# PG3_SHEET1.net
KiCad netlist of a schematic drawn in Altium Designer
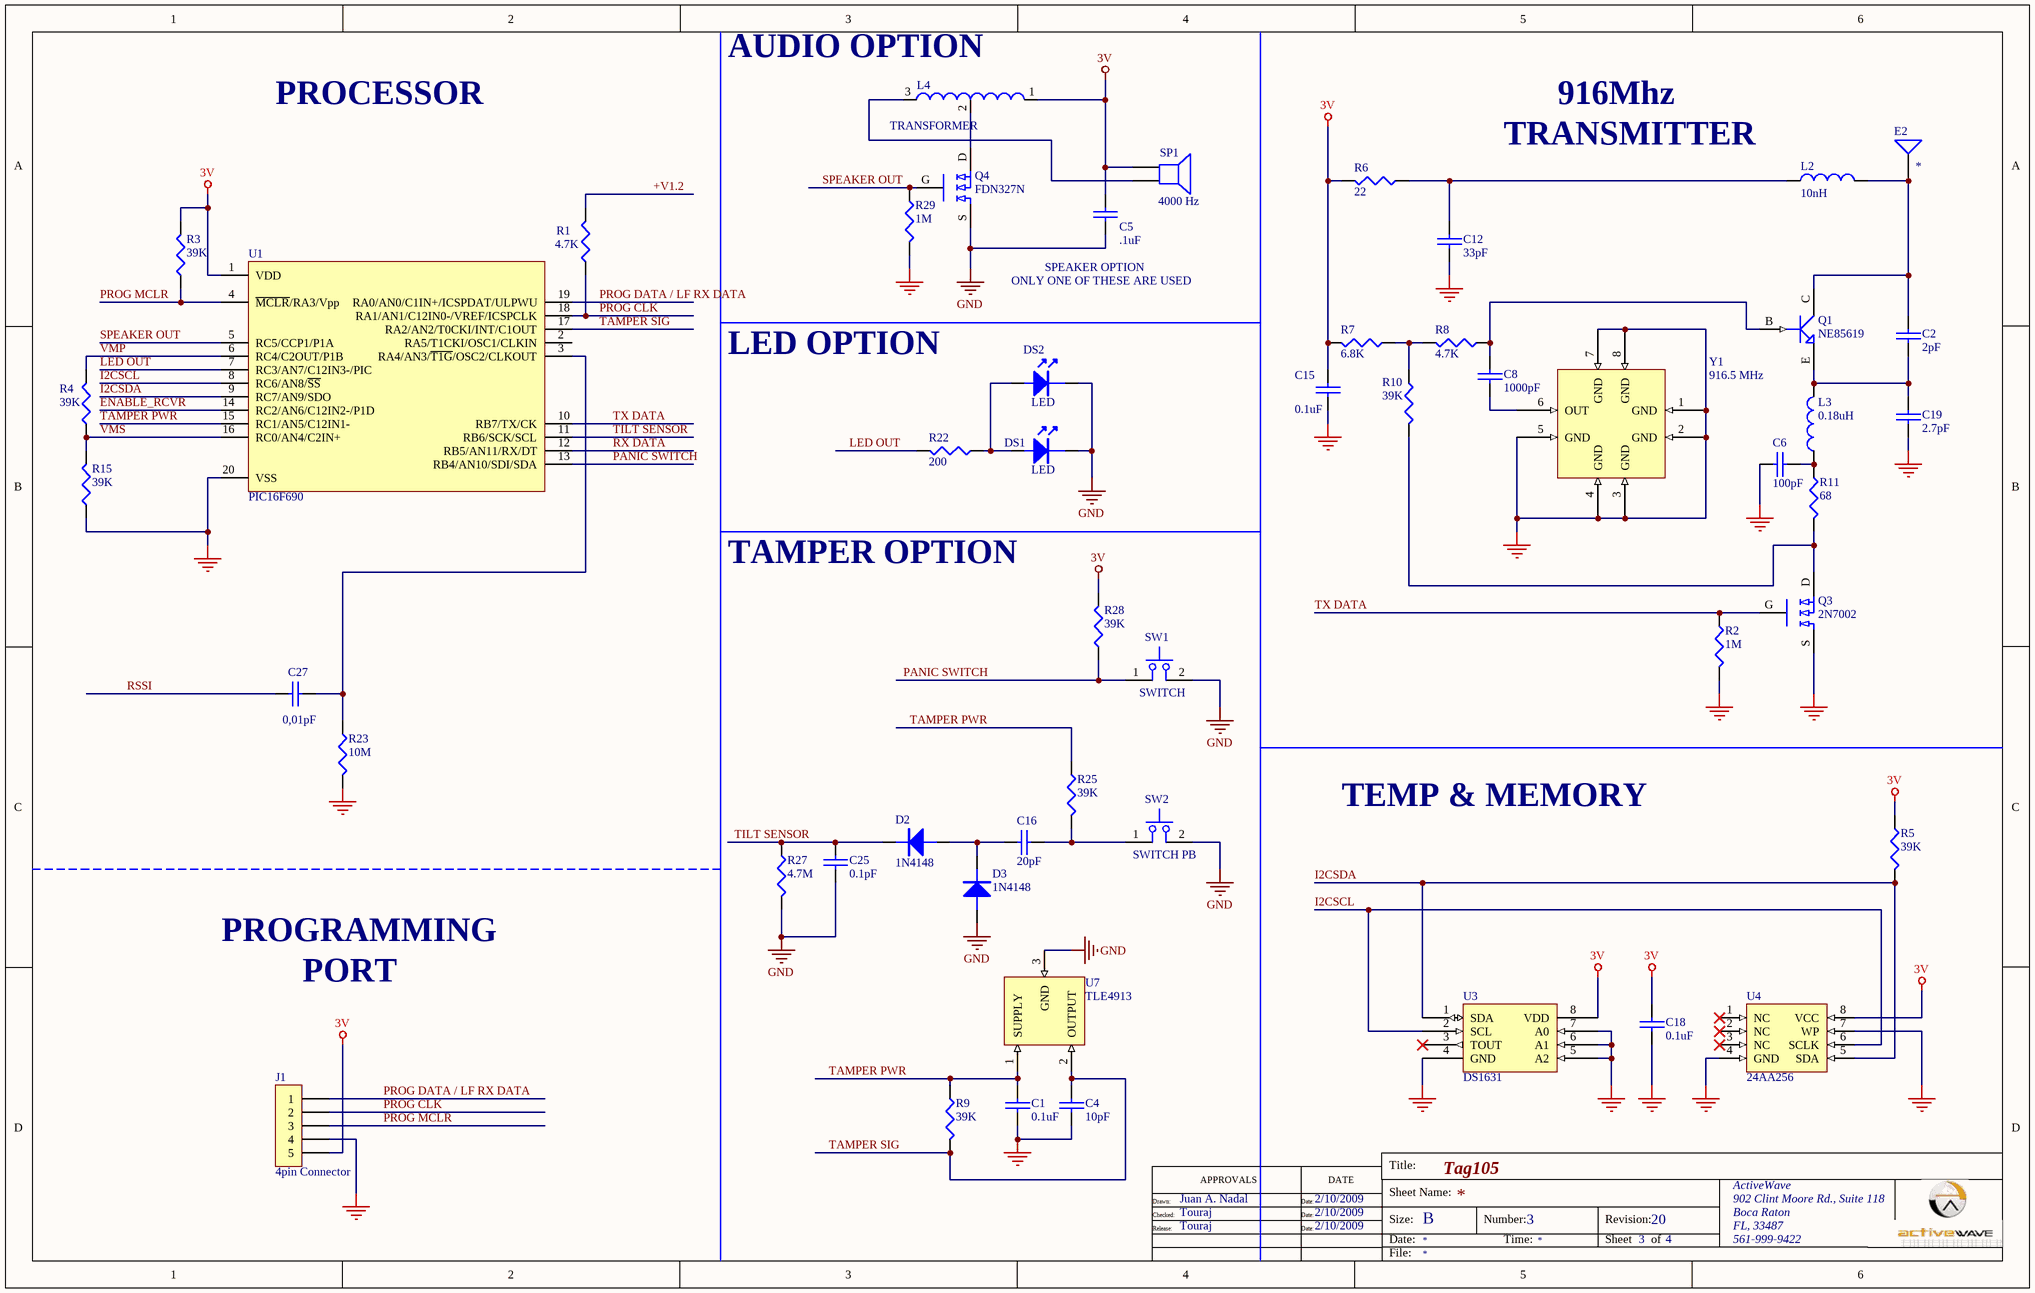
[diagram p0: PG3 SHEET1.schdoc]

(export (version "E")
  (design (tool "Eeschema 10.0.6"))
  (components
    (comp (ref "C1")
      (value "0.1uF")
      (footprint "0603")
      (description "Capacitor")
      (libsource (lib "ActiveWave MasterLib") (part "CAP-0603"))
    )
    (comp (ref "C2")
      (value "2pF")
      (footprint "0603")
      (description "Capacitor")
      (libsource (lib "ActiveWave MasterLib") (part "CAP-0603"))
    )
    (comp (ref "C4")
      (value "10pF")
      (footprint "0603")
      (description "Capacitor")
      (libsource (lib "ActiveWave MasterLib") (part "CAP-0603"))
    )
    (comp (ref "C5")
      (value ".1uF")
      (footprint "0603")
      (description "Capacitor")
      (libsource (lib "ActiveWave MasterLib") (part "CAP-0603"))
    )
    (comp (ref "C6")
      (value "100pF")
      (footprint "0603")
      (description "Capacitor")
      (libsource (lib "ActiveWave MasterLib") (part "CAP-0603"))
    )
    (comp (ref "C8")
      (value "1000pF")
      (footprint "0603")
      (description "Capacitor")
      (libsource (lib "ActiveWave MasterLib") (part "CAP-0603"))
    )
    (comp (ref "C12")
      (value "33pF")
      (footprint "0603")
      (description "Capacitor")
      (libsource (lib "ActiveWave MasterLib") (part "CAP-0603"))
    )
    (comp (ref "C15")
      (value "0.1uF")
      (footprint "0603")
      (description "Capacitor")
      (libsource (lib "ActiveWave MasterLib") (part "CAP-0603"))
    )
    (comp (ref "C16")
      (value "20pF")
      (footprint "0603")
      (description "Capacitor")
      (libsource (lib "ActiveWave MasterLib") (part "CAP-0603"))
    )
    (comp (ref "C18")
      (value "0.1uF")
      (footprint "0603")
      (description "Capacitor")
      (libsource (lib "ActiveWave MasterLib") (part "CAP-0603"))
    )
    (comp (ref "C19")
      (value "2.7pF")
      (footprint "0603")
      (description "Capacitor")
      (libsource (lib "ActiveWave MasterLib") (part "CAP-0603"))
    )
    (comp (ref "C25")
      (value "0.1pF")
      (footprint "0603")
      (description "Capacitor")
      (libsource (lib "ActiveWave MasterLib") (part "CAP-0603"))
    )
    (comp (ref "C27")
      (value "0,01pF")
      (footprint "0603")
      (description "Capacitor")
      (libsource (lib "ActiveWave MasterLib") (part "CAP-0603"))
    )
    (comp (ref "D2")
      (value "1N4148")
      (footprint "sod123_021405")
      (libsource (lib "ActiveWave MasterLib") (part "DIODE"))
    )
    (comp (ref "D3")
      (value "1N4148")
      (footprint "sod123_021405")
      (libsource (lib "ActiveWave MasterLib") (part "DIODE"))
    )
    (comp (ref "DS1")
      (value "LED")
      (footprint "404-1032-2-ND")
      (libsource (lib "ActiveWave MasterLib") (part "LED"))
    )
    (comp (ref "DS2")
      (value "LED")
      (footprint "LCE-358RP")
      (description "X-Bring Red Power SMD LED Emitter")
      (fields (field (name "MANUFACTURER") "L.C. LED"))
      (libsource (lib "ActiveWave MasterLib") (part "LCE-358RP"))
    )
    (comp (ref "E2")
      (value "*")
      (footprint "Antenna1")
      (fields (field (name "ALTIUM_VALUE") "*"))
      (libsource (lib "ActiveWave MasterLib") (part "Antenna1"))
    )
    (comp (ref "J1")
      (value "4pin Connector")
      (footprint "1X5 HEADER")
      (description "Connector")
      (libsource (lib "ActiveWave MasterLib") (part "CON5-1"))
    )
    (comp (ref "L2")
      (value "10nH")
      (footprint "0603")
      (libsource (lib "ActiveWave MasterLib") (part "INDUCTOR"))
    )
    (comp (ref "L3")
      (value "0.18uH")
      (footprint "0603")
      (libsource (lib "ActiveWave MasterLib") (part "INDUCTOR"))
    )
    (comp (ref "L4")
      (value "TRANSFORMER")
      (footprint "COIL_6mmx6mm_011012")
      (libsource (lib "ActiveWave MasterLib") (part "INDUCTOR_V2"))
    )
    (comp (ref "Q1")
      (value "NE85619")
      (footprint "3 PIN ULTRA SUPER MINI MOLD")
      (description "TRANSISTOR NPN 1GHZ SMD")
      (fields (field (name "MANUFACTURER") "??????"))
      (libsource (lib "ActiveWave MasterLib") (part "NE85619"))
    )
    (comp (ref "Q3")
      (value "2N7002")
      (footprint "SOT23 FET")
      (description "N-CHANNEL ENHANCEMENT MODE FIELD EFFECT TRANSISTOR")
      (fields (field (name "MANUFACTURER") "FAIRCHILD"))
      (libsource (lib "ActiveWave MasterLib") (part "2N7002"))
    )
    (comp (ref "Q4")
      (value "FDN327N")
      (footprint "SOT23 FET")
      (description "20V N-Channel MOSFET")
      (fields (field (name "MANUFACTURER") "FAIRCHILD"))
      (libsource (lib "ActiveWave MasterLib") (part "FDN327N"))
    )
    (comp (ref "R1") (value "4.7K") (footprint "0603") (libsource (lib "*") (part "RESISTOR")))
    (comp (ref "R2") (value "1M") (libsource (lib "ActiveWave MasterLib") (part "RES-0402")))
    (comp (ref "R3")
      (value "39K")
      (footprint "0603")
      (libsource (lib "ActiveWave MasterLib") (part "RES-0603"))
    )
    (comp (ref "R4")
      (value "39K")
      (footprint "0603")
      (libsource (lib "ActiveWave MasterLib") (part "RES-0603"))
    )
    (comp (ref "R5")
      (value "39K")
      (footprint "0603")
      (libsource (lib "ActiveWave MasterLib") (part "RES-0603"))
    )
    (comp (ref "R6") (value "22") (libsource (lib "ActiveWave MasterLib") (part "RES-0402")))
    (comp (ref "R7") (value "6.8K") (libsource (lib "ActiveWave MasterLib") (part "RES-0402")))
    (comp (ref "R8") (value "4.7K") (libsource (lib "ActiveWave MasterLib") (part "RES-0402")))
    (comp (ref "R9")
      (value "39K")
      (footprint "0603")
      (libsource (lib "ActiveWave MasterLib") (part "RES-0603"))
    )
    (comp (ref "R10")
      (value "39K")
      (footprint "0603")
      (libsource (lib "ActiveWave MasterLib") (part "RES-0603"))
    )
    (comp (ref "R11") (value "68") (libsource (lib "ActiveWave MasterLib") (part "RES-0402")))
    (comp (ref "R15")
      (value "39K")
      (footprint "0603")
      (libsource (lib "ActiveWave MasterLib") (part "RES-0603"))
    )
    (comp (ref "R22")
      (value "200")
      (footprint "0603")
      (libsource (lib "ActiveWave MasterLib") (part "RES-0603"))
    )
    (comp (ref "R23")
      (value "10M")
      (footprint "0603")
      (libsource (lib "ActiveWave MasterLib") (part "RES-0603"))
    )
    (comp (ref "R25")
      (value "39K")
      (footprint "0603")
      (libsource (lib "ActiveWave MasterLib") (part "RES-0603"))
    )
    (comp (ref "R27")
      (value "4.7M")
      (footprint "0603")
      (libsource (lib "ActiveWave MasterLib") (part "RES-0603"))
    )
    (comp (ref "R28")
      (value "39K")
      (footprint "0603")
      (libsource (lib "ActiveWave MasterLib") (part "RES-0603"))
    )
    (comp (ref "R29")
      (value "1M")
      (footprint "0603")
      (libsource (lib "ActiveWave MasterLib") (part "RES-0402"))
    )
    (comp (ref "SP1")
      (value "4000 Hz")
      (footprint "SPEAKER 12mmx12mm_011012")
      (description "Surface Mount Transducer")
      (fields (field (name "MANUFACTURER") "PUI Audio"))
      (libsource (lib "ActiveWave MasterLib") (part "SMT-1028-S-R"))
    )
    (comp (ref "SW1")
      (value "SWITCH")
      (footprint "SWITCH PB REVERSED_082907")
      (libsource (lib "ActiveWave MasterLib") (part "SWITCH"))
    )
    (comp (ref "SW2")
      (value "SWITCH PB")
      (footprint "SQ-SEN-200")
      (libsource (lib "ActiveWave MasterLib") (part "SWITCH PB"))
    )
    (comp (ref "U1")
      (value "PIC16F690")
      (footprint "SSOP20 WIDE")
      (description "Microcontrollers (MCU) 7KB FL 256R 18 I/O")
      (fields (field (name "MANUFACTURER") "Microchip"))
      (libsource (lib "ActiveWave MasterLib") (part "PIC16F690-E/P"))
    )
    (comp (ref "U3")
      (value "DS1631")
      (footprint "SO8 SMALL")
      (description "High-Precision Digital Thermometer and Thermostat")
      (fields (field (name "MANUFACTURER") "DALLAS SEMICONDUCTOR"))
      (libsource (lib "ActiveWave MasterLib") (part "DS1631"))
    )
    (comp (ref "U4")
      (value "24AA256")
      (footprint "SO8")
      (description "24AA256 32k Microchip Serial EEPROM")
      (fields (field (name "MANUFACTURER") "Microchip"))
      (libsource (lib "ActiveWave MasterLib") (part "24AA256-I/P"))
    )
    (comp (ref "U7")
      (value "TLE4913")
      (footprint "SOT23W")
      (description "Low Power Hall Switch")
      (fields (field (name "MANUFACTURER") "Infineon Technologies AG"))
      (libsource (lib "ActiveWave MasterLib") (part "TLE4913"))
    )
    (comp (ref "Y1")
      (value "916.5 MHz")
      (footprint "RESONATOR")
      (description "916.5 MHz Saw Resonator")
      (fields (field (name "MANUFACTURER") "??????"))
      (libsource (lib "ActiveWave MasterLib") (part "RESONATOR"))
    )
  )
  (nets
    (net (code "1") (name "/+V1.2") (class "Default")
      (node (ref "R1") (pin "2") (pinfunction "2_2") (pintype "passive"))
    )
    (net (code "2") (name "/ENABLE_RCVR") (class "Default")
      (node (ref "U1") (pin "14") (pinfunction "RC2/AN6/C12IN2-/P1D_14") (pintype "passive"))
    )
    (net (code "3") (name "/I2CSCL") (class "Default")
      (node (ref "U1") (pin "8") (pinfunction "RC6/AN8/~{SS}_8") (pintype "passive"))
      (node (ref "U3") (pin "2") (pinfunction "SCL_2") (pintype "input"))
      (node (ref "U4") (pin "6") (pinfunction "SCLK_6") (pintype "input"))
    )
    (net (code "4") (name "/I2CSDA") (class "Default")
      (node (ref "R5") (pin "2") (pinfunction "2_2") (pintype "passive"))
      (node (ref "U1") (pin "9") (pinfunction "RC7/AN9/SDO_9") (pintype "passive"))
      (node (ref "U3") (pin "1") (pinfunction "SDA_1") (pintype "bidirectional"))
      (node (ref "U4") (pin "5") (pinfunction "SDA_5") (pintype "input"))
    )
    (net (code "5") (name "/LED OUT") (class "Default")
      (node (ref "R22") (pin "2") (pinfunction "2_2") (pintype "passive"))
      (node (ref "U1") (pin "7") (pinfunction "RC3/AN7/C12IN3-/PIC_7") (pintype "passive"))
    )
    (net (code "6") (name "/PANIC SWITCH") (class "Default")
      (node (ref "R28") (pin "1") (pinfunction "1_1") (pintype "passive"))
      (node (ref "SW1") (pin "1") (pinfunction "1_1") (pintype "passive"))
      (node (ref "U1") (pin "13") (pinfunction "RB4/AN10/SDI/SDA_13") (pintype "passive"))
    )
    (net (code "7") (name "/PROG CLK") (class "Default")
      (node (ref "J1") (pin "2") (pinfunction "2_2") (pintype "passive"))
      (node (ref "R1") (pin "1") (pinfunction "1_1") (pintype "passive"))
      (node (ref "U1") (pin "18") (pinfunction "RA1/AN1/C12IN0-/VREF/ICSPCLK_18") (pintype "passive"))
    )
    (net (code "8") (name "/PROG DATA {slash} LF RX DATA") (class "Default")
      (node (ref "J1") (pin "1") (pinfunction "1_1") (pintype "passive"))
      (node (ref "U1") (pin "19") (pinfunction "RA0/AN0/C1IN+/ICSPDAT/ULPWU_19") (pintype "passive"))
    )
    (net (code "9") (name "/PROG MCLR") (class "Default")
      (node (ref "J1") (pin "3") (pinfunction "3_3") (pintype "passive"))
      (node (ref "R3") (pin "1") (pinfunction "1_1") (pintype "passive"))
      (node (ref "U1") (pin "4") (pinfunction "~{MCLR}/RA3/Vpp_4") (pintype "passive"))
    )
    (net (code "10") (name "/RSSI") (class "Default")
      (node (ref "C27") (pin "1") (pinfunction "1_1") (pintype "passive"))
    )
    (net (code "11") (name "/RX DATA") (class "Default")
      (node (ref "U1") (pin "12") (pinfunction "RB5/AN11/RX/DT_12") (pintype "passive"))
    )
    (net (code "12") (name "/SPEAKER OUT") (class "Default")
      (node (ref "Q4") (pin "G") (pinfunction "G_G") (pintype "passive"))
      (node (ref "R29") (pin "1") (pinfunction "1_1") (pintype "passive"))
      (node (ref "U1") (pin "5") (pinfunction "RC5/CCP1/P1A_5") (pintype "passive"))
    )
    (net (code "13") (name "/TAMPER PWR") (class "Default")
      (node (ref "C1") (pin "1") (pinfunction "1_1") (pintype "passive"))
      (node (ref "R25") (pin "1") (pinfunction "1_1") (pintype "passive"))
      (node (ref "R9") (pin "1") (pinfunction "1_1") (pintype "passive"))
      (node (ref "U1") (pin "15") (pinfunction "RC1/AN5/C12IN1-_15") (pintype "passive"))
      (node (ref "U7") (pin "1") (pinfunction "SUPPLY_1") (pintype "input"))
    )
    (net (code "14") (name "/TAMPER SIG") (class "Default")
      (node (ref "C4") (pin "1") (pinfunction "1_1") (pintype "passive"))
      (node (ref "R9") (pin "2") (pinfunction "2_2") (pintype "passive"))
      (node (ref "U1") (pin "17") (pinfunction "RA2/AN2/T0CKI/INT/C1OUT_17") (pintype "passive"))
      (node (ref "U7") (pin "2") (pinfunction "OUTPUT_2") (pintype "input"))
    )
    (net (code "15") (name "/TILT SENSOR") (class "Default")
      (node (ref "C25") (pin "1") (pinfunction "1_1") (pintype "passive"))
      (node (ref "D2") (pin "K") (pinfunction "K_K") (pintype "passive"))
      (node (ref "R27") (pin "1") (pinfunction "1_1") (pintype "passive"))
      (node (ref "U1") (pin "11") (pinfunction "RB6/SCK/SCL_11") (pintype "passive"))
    )
    (net (code "16") (name "/TX DATA") (class "Default")
      (node (ref "Q3") (pin "G") (pinfunction "G_G") (pintype "passive"))
      (node (ref "R2") (pin "1") (pinfunction "1_1") (pintype "passive"))
      (node (ref "U1") (pin "10") (pinfunction "RB7/TX/CK_10") (pintype "passive"))
    )
    (net (code "17") (name "/VMP") (class "Default")
      (node (ref "R4") (pin "2") (pinfunction "2_2") (pintype "passive"))
      (node (ref "U1") (pin "6") (pinfunction "RC4/C2OUT/P1B_6") (pintype "passive"))
    )
    (net (code "18") (name "/VMS") (class "Default")
      (node (ref "R15") (pin "2") (pinfunction "2_2") (pintype "passive"))
      (node (ref "R4") (pin "1") (pinfunction "1_1") (pintype "passive"))
      (node (ref "U1") (pin "16") (pinfunction "RC0/AN4/C2IN+_16") (pintype "passive"))
    )
    (net (code "19") (name "3V") (class "Default")
      (node (ref "C15") (pin "1") (pinfunction "1_1") (pintype "passive"))
      (node (ref "C18") (pin "1") (pinfunction "1_1") (pintype "passive"))
      (node (ref "C5") (pin "1") (pinfunction "1_1") (pintype "passive"))
      (node (ref "J1") (pin "5") (pinfunction "5_5") (pintype "passive"))
      (node (ref "L4") (pin "1") (pinfunction "1_1") (pintype "passive"))
      (node (ref "R28") (pin "2") (pinfunction "2_2") (pintype "passive"))
      (node (ref "R3") (pin "2") (pinfunction "2_2") (pintype "passive"))
      (node (ref "R5") (pin "1") (pinfunction "1_1") (pintype "passive"))
      (node (ref "R6") (pin "2") (pinfunction "2_2") (pintype "passive"))
      (node (ref "R7") (pin "2") (pinfunction "2_2") (pintype "passive"))
      (node (ref "SP1") (pin "1") (pinfunction "1_1") (pintype "passive"))
      (node (ref "U1") (pin "1") (pinfunction "VDD_1") (pintype "passive"))
      (node (ref "U3") (pin "8") (pinfunction "VDD_8") (pintype "power_in"))
      (node (ref "U4") (pin "8") (pinfunction "VCC_8") (pintype "input"))
    )
    (net (code "20") (name "GND") (class "Default")
      (node (ref "C1") (pin "2") (pinfunction "2_2") (pintype "passive"))
      (node (ref "C12") (pin "2") (pinfunction "2_2") (pintype "passive"))
      (node (ref "C15") (pin "2") (pinfunction "2_2") (pintype "passive"))
      (node (ref "C18") (pin "2") (pinfunction "2_2") (pintype "passive"))
      (node (ref "C19") (pin "2") (pinfunction "2_2") (pintype "passive"))
      (node (ref "C25") (pin "2") (pinfunction "2_2") (pintype "passive"))
      (node (ref "C4") (pin "2") (pinfunction "2_2") (pintype "passive"))
      (node (ref "C5") (pin "2") (pinfunction "2_2") (pintype "passive"))
      (node (ref "C6") (pin "2") (pinfunction "2_2") (pintype "passive"))
      (node (ref "D3") (pin "A") (pinfunction "A_A") (pintype "passive"))
      (node (ref "DS1") (pin "K") (pinfunction "K_K") (pintype "passive"))
      (node (ref "DS2") (pin "2") (pinfunction "2_2") (pintype "passive"))
      (node (ref "J1") (pin "4") (pinfunction "4_4") (pintype "passive"))
      (node (ref "Q3") (pin "S") (pinfunction "S_S") (pintype "passive"))
      (node (ref "Q4") (pin "S") (pinfunction "S_S") (pintype "passive"))
      (node (ref "R15") (pin "1") (pinfunction "1_1") (pintype "passive"))
      (node (ref "R2") (pin "2") (pinfunction "2_2") (pintype "passive"))
      (node (ref "R23") (pin "2") (pinfunction "2_2") (pintype "passive"))
      (node (ref "R27") (pin "2") (pinfunction "2_2") (pintype "passive"))
      (node (ref "R29") (pin "2") (pinfunction "2_2") (pintype "passive"))
      (node (ref "SW1") (pin "2") (pinfunction "2_2") (pintype "passive"))
      (node (ref "SW2") (pin "2") (pinfunction "2_2") (pintype "passive"))
      (node (ref "U1") (pin "20") (pinfunction "VSS_20") (pintype "passive"))
      (node (ref "U3") (pin "4") (pinfunction "GND_4") (pintype "power_in"))
      (node (ref "U3") (pin "5") (pinfunction "A2_5") (pintype "input"))
      (node (ref "U3") (pin "6") (pinfunction "A1_6") (pintype "input"))
      (node (ref "U3") (pin "7") (pinfunction "A0_7") (pintype "input"))
      (node (ref "U4") (pin "4") (pinfunction "GND_4") (pintype "input"))
      (node (ref "U4") (pin "7") (pinfunction "WP_7") (pintype "input"))
      (node (ref "U7") (pin "3") (pinfunction "GND_3") (pintype "input"))
      (node (ref "Y1") (pin "1") (pinfunction "GND_1") (pintype "input"))
      (node (ref "Y1") (pin "2") (pinfunction "GND_2") (pintype "input"))
      (node (ref "Y1") (pin "3") (pinfunction "GND_3") (pintype "input"))
      (node (ref "Y1") (pin "4") (pinfunction "GND_4") (pintype "input"))
      (node (ref "Y1") (pin "5") (pinfunction "GND_5") (pintype "input"))
      (node (ref "Y1") (pin "7") (pinfunction "GND_7") (pintype "input"))
      (node (ref "Y1") (pin "8") (pinfunction "GND_8") (pintype "input"))
    )
    (net (code "21") (name "Net-(C2-Pad1)") (class "Default")
      (node (ref "C2") (pin "1") (pinfunction "1_1") (pintype "passive"))
      (node (ref "E2") (pin "1") (pinfunction "1_1") (pintype "passive"))
      (node (ref "L2") (pin "2") (pinfunction "2_2") (pintype "passive"))
      (node (ref "Q1") (pin "C") (pinfunction "C_C") (pintype "passive"))
    )
    (net (code "22") (name "Net-(C6-Pad1)") (class "Default")
      (node (ref "C6") (pin "1") (pinfunction "1_1") (pintype "passive"))
      (node (ref "L3") (pin "1") (pinfunction "1_1") (pintype "passive"))
      (node (ref "R11") (pin "1") (pinfunction "1_1") (pintype "passive"))
    )
    (net (code "23") (name "Net-(C8-Pad1)") (class "Default")
      (node (ref "C8") (pin "1") (pinfunction "1_1") (pintype "passive"))
      (node (ref "Q1") (pin "B") (pinfunction "B_B") (pintype "input"))
      (node (ref "R8") (pin "1") (pinfunction "1_1") (pintype "passive"))
    )
    (net (code "24") (name "Net-(C12-Pad1)") (class "Default")
      (node (ref "C12") (pin "1") (pinfunction "1_1") (pintype "passive"))
      (node (ref "L2") (pin "1") (pinfunction "1_1") (pintype "passive"))
      (node (ref "R6") (pin "1") (pinfunction "1_1") (pintype "passive"))
    )
    (net (code "25") (name "Net-(C16-Pad1)") (class "Default")
      (node (ref "C16") (pin "1") (pinfunction "1_1") (pintype "passive"))
      (node (ref "R25") (pin "2") (pinfunction "2_2") (pintype "passive"))
      (node (ref "SW2") (pin "1") (pinfunction "1_1") (pintype "passive"))
    )
    (net (code "26") (name "Net-(C16-Pad2)") (class "Default")
      (node (ref "C16") (pin "2") (pinfunction "2_2") (pintype "passive"))
      (node (ref "D2") (pin "A") (pinfunction "A_A") (pintype "passive"))
      (node (ref "D3") (pin "K") (pinfunction "K_K") (pintype "passive"))
    )
    (net (code "27") (name "Net-(C19-Pad1)") (class "Default")
      (node (ref "C19") (pin "1") (pinfunction "1_1") (pintype "passive"))
      (node (ref "C2") (pin "2") (pinfunction "2_2") (pintype "passive"))
      (node (ref "L3") (pin "2") (pinfunction "2_2") (pintype "passive"))
      (node (ref "Q1") (pin "E") (pinfunction "E_E") (pintype "passive"))
    )
    (net (code "28") (name "Net-(DS1-PadA)") (class "Default")
      (node (ref "DS1") (pin "A") (pinfunction "A_A") (pintype "passive"))
      (node (ref "DS2") (pin "1") (pinfunction "1_1") (pintype "passive"))
      (node (ref "R22") (pin "1") (pinfunction "1_1") (pintype "passive"))
    )
    (net (code "29") (name "Net-(L4-Pad2)") (class "Default")
      (node (ref "L4") (pin "2") (pinfunction "2_2") (pintype "passive"))
      (node (ref "Q4") (pin "D") (pinfunction "D_D") (pintype "passive"))
    )
    (net (code "30") (name "Net-(L4-Pad3)") (class "Default")
      (node (ref "L4") (pin "3") (pinfunction "3_3") (pintype "passive"))
      (node (ref "SP1") (pin "2") (pinfunction "2_2") (pintype "passive"))
    )
    (net (code "31") (name "Net-(Q3-PadD)") (class "Default")
      (node (ref "Q3") (pin "D") (pinfunction "D_D") (pintype "passive"))
      (node (ref "R10") (pin "2") (pinfunction "2_2") (pintype "passive"))
      (node (ref "R11") (pin "2") (pinfunction "2_2") (pintype "passive"))
    )
    (net (code "32") (name "Net-(R10-Pad1)") (class "Default")
      (node (ref "R10") (pin "1") (pinfunction "1_1") (pintype "passive"))
      (node (ref "R7") (pin "1") (pinfunction "1_1") (pintype "passive"))
      (node (ref "R8") (pin "2") (pinfunction "2_2") (pintype "passive"))
    )
    (net (code "33") (name "Net-(U1-RA4{slash}AN3{slash}~{T1G}{slash}OSC2{slash}CLKOUT)") (class "Default")
      (node (ref "C27") (pin "2") (pinfunction "2_2") (pintype "passive"))
      (node (ref "R23") (pin "1") (pinfunction "1_1") (pintype "passive"))
      (node (ref "U1") (pin "3") (pinfunction "RA4/AN3/~{T1G}/OSC2/CLKOUT_3") (pintype "passive"))
    )
    (net (code "34") (name "Net-(Y1-OUT)") (class "Default")
      (node (ref "C8") (pin "2") (pinfunction "2_2") (pintype "passive"))
      (node (ref "Y1") (pin "6") (pinfunction "OUT_6") (pintype "input"))
    )
    (net (code "35") (name "unconnected-(U1-RA5{slash}T1CKI{slash}OSC1{slash}CLKIN-Pad2)") (class "Default")
      (node (ref "U1") (pin "2") (pinfunction "RA5/T1CKI/OSC1/CLKIN_2") (pintype "passive"))
    )
    (net (code "36") (name "unconnected-(U3-TOUT-Pad3)") (class "Default")
      (node (ref "U3") (pin "3") (pinfunction "TOUT_3") (pintype "output+no_connect"))
    )
    (net (code "37") (name "unconnected-(U4-NC-Pad1)") (class "Default")
      (node (ref "U4") (pin "1") (pinfunction "NC_1") (pintype "input+no_connect"))
    )
    (net (code "38") (name "unconnected-(U4-NC-Pad2)") (class "Default")
      (node (ref "U4") (pin "2") (pinfunction "NC_2") (pintype "input+no_connect"))
    )
    (net (code "39") (name "unconnected-(U4-NC-Pad3)") (class "Default")
      (node (ref "U4") (pin "3") (pinfunction "NC_3") (pintype "input+no_connect"))
    )
  )
)
